# CuC_PSU.net
KiCad netlist of a schematic drawn in Altium Designer
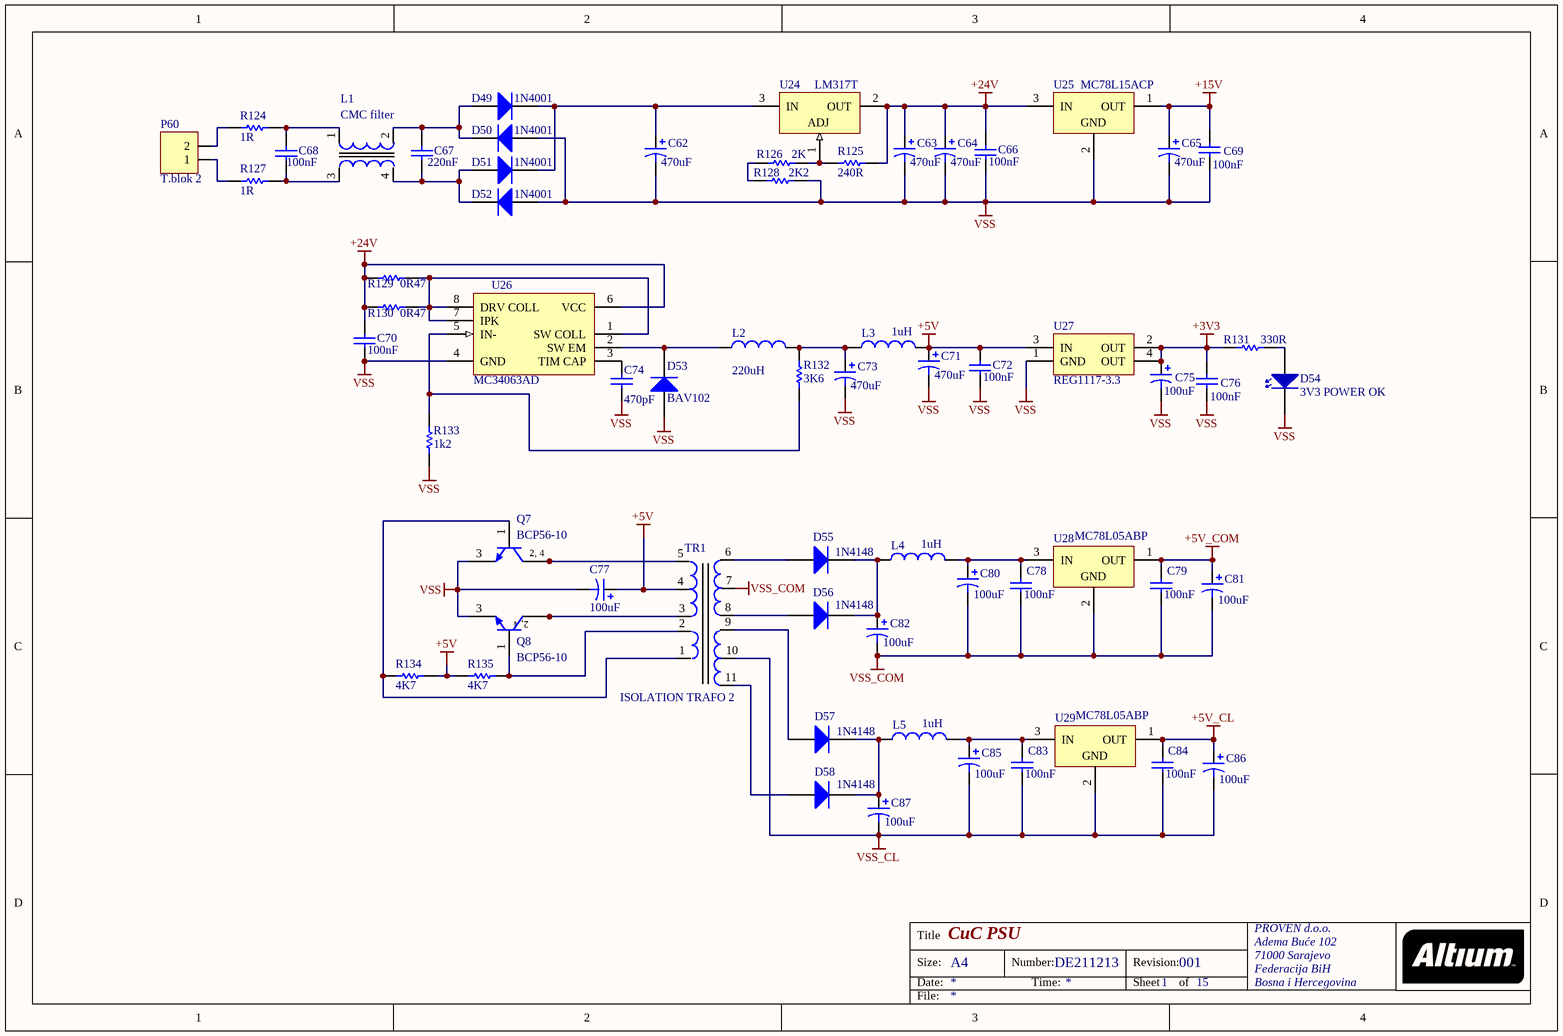
[diagram p0: CuC_PSU.SchDoc]

(export (version "E")
  (design (tool "Eeschema 10.0.6"))
  (components
    (comp (ref "C62")
      (value "470uF")
      (footprint "CAPPR5-10X16")
      (description "Aluminum Electrolytic Capacitor, Radial Style with Long Leads: 470uF, 35V")
      (fields (field (name "PUBLISHER") "Altium Limited"))
      (libsource (lib "Vishay Roederstein Electrolytic Radial-Lead Capacitor") (part "EKA00DD347F00"))
    )
    (comp (ref "C63")
      (value "470uF")
      (footprint "CAPPR5-10X16")
      (description "Aluminum Electrolytic Capacitor, Radial Style with Long Leads: 470uF, 35V")
      (fields (field (name "PUBLISHER") "Altium Limited"))
      (libsource (lib "Vishay Roederstein Electrolytic Radial-Lead Capacitor") (part "EKA00DD347F00"))
    )
    (comp (ref "C64")
      (value "470uF")
      (footprint "CAPPR5-10X16")
      (description "Aluminum Electrolytic Capacitor, Radial Style with Long Leads: 470uF, 35V")
      (fields (field (name "PUBLISHER") "Altium Limited"))
      (libsource (lib "Vishay Roederstein Electrolytic Radial-Lead Capacitor") (part "EKA00DD347F00"))
    )
    (comp (ref "C65")
      (value "470uF")
      (footprint "CAPPR5-10X16")
      (description "Aluminum Electrolytic Capacitor, Radial Style with Long Leads: 470uF, 35V")
      (fields (field (name "PUBLISHER") "Altium Limited"))
      (libsource (lib "Vishay Roederstein Electrolytic Radial-Lead Capacitor") (part "EKA00DD347F00"))
    )
    (comp (ref "C66")
      (value "100nF")
      (footprint "1206")
      (description "Ceramic Chip Capacitor - Standard")
      (fields (field (name "PUBLISHER") "Altium Limited"))
      (libsource (lib "KEMET Chip Capacitor") (part "C1206"))
    )
    (comp (ref "C67")
      (value "220nF")
      (footprint "VP60-3.6")
      (description "Dipped Radial Multilayer Ceramic Capacitor COG (NPO): 68nF, 50/63V")
      (fields (field (name "PUBLISHER") "Altium Limited"))
      (libsource (lib "Vishay Vitramon Ceramic Dipped Capacitor") (part "VP60BA683KA"))
    )
    (comp (ref "C68")
      (value "100nF")
      (footprint "VP60-3.6")
      (description "Dipped Radial Multilayer Ceramic Capacitor COG (NPO): 68nF, 50/63V")
      (fields (field (name "PUBLISHER") "Altium Limited"))
      (libsource (lib "Vishay Vitramon Ceramic Dipped Capacitor") (part "VP60BA683KA"))
    )
    (comp (ref "C69")
      (value "100nF")
      (footprint "1206")
      (description "Ceramic Chip Capacitor - Standard")
      (fields (field (name "PUBLISHER") "Altium Limited"))
      (libsource (lib "KEMET Chip Capacitor") (part "C1206"))
    )
    (comp (ref "C70")
      (value "100nF")
      (footprint "1206")
      (description "Ceramic Chip Capacitor - Standard")
      (fields (field (name "PUBLISHER") "Altium Limited"))
      (libsource (lib "KEMET Chip Capacitor") (part "C1206"))
    )
    (comp (ref "C71")
      (value "470uF")
      (footprint "CAPPR5-10X16")
      (description "Aluminum Electrolytic Capacitor, Radial Style with Long Leads: 470uF, 35V")
      (fields (field (name "PUBLISHER") "Altium Limited"))
      (libsource (lib "Vishay Roederstein Electrolytic Radial-Lead Capacitor") (part "EKA00DD347F00"))
    )
    (comp (ref "C72")
      (value "100nF")
      (footprint "1206")
      (description "Ceramic Chip Capacitor - Standard")
      (fields (field (name "PUBLISHER") "Altium Limited"))
      (libsource (lib "KEMET Chip Capacitor") (part "C1206"))
    )
    (comp (ref "C73")
      (value "470uF")
      (footprint "CAPPR5-10X16")
      (description "Aluminum Electrolytic Capacitor, Radial Style with Long Leads: 470uF, 35V")
      (fields (field (name "PUBLISHER") "Altium Limited"))
      (libsource (lib "Vishay Roederstein Electrolytic Radial-Lead Capacitor") (part "EKA00DD347F00"))
    )
    (comp (ref "C74")
      (value "470pF")
      (footprint "0805")
      (description "Ceramic Chip Capacitor - Standard")
      (fields (field (name "PUBLISHER") "Altium Limited"))
      (libsource (lib "KEMET Chip Capacitor") (part "C0805"))
    )
    (comp (ref "C75")
      (value "100uF")
      (footprint "CAPPR2-5X11")
      (description "Aluminum Electrolytic Capacitor, Radial Style with Long Leads: 100uF, 16V")
      (fields (field (name "PUBLISHER") "Altium Limited"))
      (libsource (lib "Vishay Roederstein Electrolytic Radial-Lead Capacitor") (part "EKA00AA310D00"))
    )
    (comp (ref "C76")
      (value "100nF")
      (footprint "1206")
      (description "Ceramic Chip Capacitor - Standard")
      (fields (field (name "PUBLISHER") "Altium Limited"))
      (libsource (lib "KEMET Chip Capacitor") (part "C1206"))
    )
    (comp (ref "C77")
      (value "100uF")
      (footprint "CAPPR2-5X11")
      (description "Aluminum Electrolytic Capacitor, Radial Style with Long Leads: 100uF, 16V")
      (fields (field (name "PUBLISHER") "Altium Limited"))
      (libsource (lib "Vishay Roederstein Electrolytic Radial-Lead Capacitor") (part "EKA00AA310D00"))
    )
    (comp (ref "C78")
      (value "100nF")
      (footprint "1206")
      (description "Ceramic Chip Capacitor - Standard")
      (fields (field (name "PUBLISHER") "Altium Limited"))
      (libsource (lib "KEMET Chip Capacitor") (part "C1206"))
    )
    (comp (ref "C79")
      (value "100nF")
      (footprint "1206")
      (description "Ceramic Chip Capacitor - Standard")
      (fields (field (name "PUBLISHER") "Altium Limited"))
      (libsource (lib "KEMET Chip Capacitor") (part "C1206"))
    )
    (comp (ref "C80")
      (value "100uF")
      (footprint "CAPPR2-5X11")
      (description "Aluminum Electrolytic Capacitor, Radial Style with Long Leads: 100uF, 16V")
      (fields (field (name "PUBLISHER") "Altium Limited"))
      (libsource (lib "Vishay Roederstein Electrolytic Radial-Lead Capacitor") (part "EKA00AA310D00"))
    )
    (comp (ref "C81")
      (value "100uF")
      (footprint "CAPPR2-5X11")
      (description "Aluminum Electrolytic Capacitor, Radial Style with Long Leads: 100uF, 16V")
      (fields (field (name "PUBLISHER") "Altium Limited"))
      (libsource (lib "Vishay Roederstein Electrolytic Radial-Lead Capacitor") (part "EKA00AA310D00"))
    )
    (comp (ref "C82")
      (value "100uF")
      (footprint "CAPPR2-5X11")
      (description "Aluminum Electrolytic Capacitor, Radial Style with Long Leads: 100uF, 16V")
      (fields (field (name "PUBLISHER") "Altium Limited"))
      (libsource (lib "Vishay Roederstein Electrolytic Radial-Lead Capacitor") (part "EKA00AA310D00"))
    )
    (comp (ref "C83")
      (value "100nF")
      (footprint "1206")
      (description "Ceramic Chip Capacitor - Standard")
      (fields (field (name "PUBLISHER") "Altium Limited"))
      (libsource (lib "KEMET Chip Capacitor") (part "C1206"))
    )
    (comp (ref "C84")
      (value "100nF")
      (footprint "1206")
      (description "Ceramic Chip Capacitor - Standard")
      (fields (field (name "PUBLISHER") "Altium Limited"))
      (libsource (lib "KEMET Chip Capacitor") (part "C1206"))
    )
    (comp (ref "C85")
      (value "100uF")
      (footprint "CAPPR2-5X11")
      (description "Aluminum Electrolytic Capacitor, Radial Style with Long Leads: 100uF, 16V")
      (fields (field (name "PUBLISHER") "Altium Limited"))
      (libsource (lib "Vishay Roederstein Electrolytic Radial-Lead Capacitor") (part "EKA00AA310D00"))
    )
    (comp (ref "C86")
      (value "100uF")
      (footprint "CAPPR2-5X11")
      (description "Aluminum Electrolytic Capacitor, Radial Style with Long Leads: 100uF, 16V")
      (fields (field (name "PUBLISHER") "Altium Limited"))
      (libsource (lib "Vishay Roederstein Electrolytic Radial-Lead Capacitor") (part "EKA00AA310D00"))
    )
    (comp (ref "C87")
      (value "100uF")
      (footprint "CAPPR2-5X11")
      (description "Aluminum Electrolytic Capacitor, Radial Style with Long Leads: 100uF, 16V")
      (fields (field (name "PUBLISHER") "Altium Limited"))
      (libsource (lib "Vishay Roederstein Electrolytic Radial-Lead Capacitor") (part "EKA00AA310D00"))
    )
    (comp (ref "D49")
      (value "1N4001")
      (footprint "DO-41")
      (description "1 Amp General Purpose Rectifier")
      (fields (field (name "PUBLISHER") "Altium Limited"))
      (libsource (lib "Miscellaneous Devices") (part "Diode 1N4007"))
    )
    (comp (ref "D50")
      (value "1N4001")
      (footprint "DO-41")
      (description "1 Amp General Purpose Rectifier")
      (fields (field (name "PUBLISHER") "Altium Limited"))
      (libsource (lib "Miscellaneous Devices") (part "Diode 1N4007"))
    )
    (comp (ref "D51")
      (value "1N4001")
      (footprint "DO-41")
      (description "1 Amp General Purpose Rectifier")
      (fields (field (name "PUBLISHER") "Altium Limited"))
      (libsource (lib "Miscellaneous Devices") (part "Diode 1N4007"))
    )
    (comp (ref "D52")
      (value "1N4001")
      (footprint "DO-41")
      (description "1 Amp General Purpose Rectifier")
      (fields (field (name "PUBLISHER") "Altium Limited"))
      (libsource (lib "Miscellaneous Devices") (part "Diode 1N4007"))
    )
    (comp (ref "D53")
      (value "BAV102")
      (footprint "SOD80C")
      (description "General-purpose Diode")
      (fields (field (name "PUBLISHER") "Altium Limited"))
      (libsource (lib "Philips Discrete Diode - Switching") (part "BAV102"))
    )
    (comp (ref "D54")
      (value "3V3 POWER OK")
      (footprint "LED 3mm")
      (libsource (lib "ProjectLibrary") (part "LED 3mm"))
    )
    (comp (ref "D55")
      (value "1N4148")
      (footprint "DO-35")
      (description "High Conductance Fast Diode")
      (fields (field (name "PUBLISHER") "Altium Limited"))
      (libsource (lib "Miscellaneous Devices") (part "Diode 1N4148"))
    )
    (comp (ref "D56")
      (value "1N4148")
      (footprint "DO-35")
      (description "High Conductance Fast Diode")
      (fields (field (name "PUBLISHER") "Altium Limited"))
      (libsource (lib "Miscellaneous Devices") (part "Diode 1N4148"))
    )
    (comp (ref "D57")
      (value "1N4148")
      (footprint "DO-35")
      (description "High Conductance Fast Diode")
      (fields (field (name "PUBLISHER") "Altium Limited"))
      (libsource (lib "Miscellaneous Devices") (part "Diode 1N4148"))
    )
    (comp (ref "D58")
      (value "1N4148")
      (footprint "DO-35")
      (description "High Conductance Fast Diode")
      (fields (field (name "PUBLISHER") "Altium Limited"))
      (libsource (lib "Miscellaneous Devices") (part "Diode 1N4148"))
    )
    (comp (ref "L1")
      (value "CMC filter")
      (footprint "MREZNI FILTER")
      (libsource (lib "ProjectLibrary") (part "MREZNI FILTER"))
    )
    (comp (ref "L2")
      (value "220uH")
      (footprint "Miscellaneous Devices:RB5-10.5")
      (description "SMT Power Choke Coil; Size 7.3×6.6×3.0mm, ±20% Tolerance, 0.82uH, 13A")
      (fields (field (name "PUBLISHER") "Altium Limited"))
      (libsource (lib "SSM Inductor") (part "PCMC063T-R82MN"))
    )
    (comp (ref "L3")
      (value "1uH")
      (footprint "Miscellaneous Devices:RB5-10.5")
      (description "SMT Power Choke Coil; Size 7.3×6.6×3.0mm, ±20% Tolerance, 0.82uH, 13A")
      (fields (field (name "PUBLISHER") "Altium Limited"))
      (libsource (lib "SSM Inductor") (part "PCMC063T-R82MN"))
    )
    (comp (ref "L4")
      (value "1uH")
      (footprint "Miscellaneous Devices:RB5-10.5")
      (description "SMT Power Choke Coil; Size 7.3×6.6×3.0mm, ±20% Tolerance, 0.82uH, 13A")
      (fields (field (name "PUBLISHER") "Altium Limited"))
      (libsource (lib "SSM Inductor") (part "PCMC063T-R82MN"))
    )
    (comp (ref "L5")
      (value "1uH")
      (footprint "Miscellaneous Devices:RB5-10.5")
      (description "SMT Power Choke Coil; Size 7.3×6.6×3.0mm, ±20% Tolerance, 0.82uH, 13A")
      (fields (field (name "PUBLISHER") "Altium Limited"))
      (libsource (lib "SSM Inductor") (part "PCMC063T-R82MN"))
    )
    (comp (ref "P60")
      (value "T.blok 2")
      (footprint "TERMINAL BLOK 2")
      (description "Terminal blok konektor 3,5 mm")
      (libsource (lib "ProjectLibrary") (part "TERMINAL BLOK 2"))
    )
    (comp (ref "Q7")
      (value "BCP56-10")
      (footprint "SOT223_N")
      (description "NPN Medium Power Transistor")
      (fields (field (name "PUBLISHER") "Altium Limited"))
      (libsource (lib "Philips Discrete BJT - Medium Power") (part "BCP56-10"))
    )
    (comp (ref "Q8")
      (value "BCP56-10")
      (footprint "SOT223_N")
      (description "NPN Medium Power Transistor")
      (fields (field (name "PUBLISHER") "Altium Limited"))
      (libsource (lib "Philips Discrete BJT - Medium Power") (part "BCP56-10"))
    )
    (comp (ref "R124")
      (value "1R")
      (footprint "R6.35x2.3")
      (description "Metal Oxide Film Resistor, 0.1 Ohm to 47k Ohm Range, 2% and 5% Tolerance, 0.5 W")
      (fields (field (name "PUBLISHER") "Altium Limited"))
      (libsource (lib "Panasonic Resistor") (part "ERG12"))
    )
    (comp (ref "R125")
      (value "240R")
      (footprint "ERA-0805")
      (fields (field (name "PUBLISHER") "Altium Limited"))
      (libsource (lib "Panasonic Resistor") (part "ERAS"))
    )
    (comp (ref "R126")
      (value "2K")
      (footprint "ERA-0805")
      (fields (field (name "PUBLISHER") "Altium Limited"))
      (libsource (lib "Panasonic Resistor") (part "ERAS"))
    )
    (comp (ref "R127")
      (value "1R")
      (footprint "R6.35x2.3")
      (description "Metal Oxide Film Resistor, 0.1 Ohm to 47k Ohm Range, 2% and 5% Tolerance, 0.5 W")
      (fields (field (name "PUBLISHER") "Altium Limited"))
      (libsource (lib "Panasonic Resistor") (part "ERG12"))
    )
    (comp (ref "R128")
      (value "2K2")
      (footprint "ERA-0805")
      (fields (field (name "PUBLISHER") "Altium Limited"))
      (libsource (lib "Panasonic Resistor") (part "ERAS"))
    )
    (comp (ref "R129")
      (value "0R47")
      (footprint "RD6.35x2.3")
      (description "Carbon Film Resistor, 1 Ohm to 3.3M Ohm Range, 5% Tolerance, 0.5 W")
      (fields (field (name "PUBLISHER") "Altium Limited"))
      (libsource (lib "Panasonic Resistor") (part "ERDS1T"))
    )
    (comp (ref "R130")
      (value "0R47")
      (footprint "RD6.35x2.3")
      (description "Carbon Film Resistor, 1 Ohm to 3.3M Ohm Range, 5% Tolerance, 0.5 W")
      (fields (field (name "PUBLISHER") "Altium Limited"))
      (libsource (lib "Panasonic Resistor") (part "ERDS1T"))
    )
    (comp (ref "R131")
      (value "330R")
      (footprint "ERA-0603")
      (fields (field (name "PUBLISHER") "Altium Limited"))
      (libsource (lib "Panasonic Resistor") (part "ERA3Y"))
    )
    (comp (ref "R132")
      (value "3K6")
      (footprint "ERA-0805")
      (fields (field (name "PUBLISHER") "Altium Limited"))
      (libsource (lib "Panasonic Resistor") (part "ERAS"))
    )
    (comp (ref "R133")
      (value "1k2")
      (footprint "ERA-0805")
      (fields (field (name "PUBLISHER") "Altium Limited"))
      (libsource (lib "Panasonic Resistor") (part "ERAS"))
    )
    (comp (ref "R134")
      (value "4K7")
      (footprint "ERA-0805")
      (fields (field (name "PUBLISHER") "Altium Limited"))
      (libsource (lib "Panasonic Resistor") (part "ERAS"))
    )
    (comp (ref "R135")
      (value "4K7")
      (footprint "ERA-0805")
      (fields (field (name "PUBLISHER") "Altium Limited"))
      (libsource (lib "Panasonic Resistor") (part "ERAS"))
    )
    (comp (ref "TR1")
      (value "ISOLATION TRAFO 2")
      (footprint "ISOLATION TRAFO 2")
      (libsource (lib "ProjectLibrary") (part "ISOLATION TRAFO 2"))
    )
    (comp (ref "U24")
      (value "LM317T")
      (footprint "221A-04")
      (description "3-Terminal Adjustable Positive Voltage Regulator")
      (fields (field (name "PUBLISHER") "Altium Limited"))
      (libsource (lib "Motorola Power Mgt Voltage Regulator") (part "LM317T"))
    )
    (comp (ref "U25")
      (value "MC78L15ACP")
      (footprint "29-04")
      (description "3-Terminal Low-Current Positive Fixed Voltage Regulator")
      (fields (field (name "PUBLISHER") "Altium Limited"))
      (libsource (lib "Motorola Power Mgt Voltage Regulator") (part "MC78L15ACP"))
    )
    (comp (ref "U26")
      (value "MC34063AD")
      (footprint "ON Semi Power Mgt Supervisory Cct:626-05")
      (description "DC-to-DC Converter Control Circuit")
      (fields (field (name "PUBLISHER") "Altium Limited"))
      (libsource (lib "ON Semi Power Mgt DC-DC Converter") (part "MC34063AD"))
    )
    (comp (ref "U27")
      (value "REG1117-3.3")
      (footprint "ZZ311")
      (description "800mA and 1A Low Dropout Positive Regulator 2.85V, 3.3V, 5V, and Adjustable")
      (fields (field (name "PUBLISHER") "Altium Limited"))
      (libsource (lib "BB Power Mgt Voltage Regulator") (part "REG1117-3.3"))
    )
    (comp (ref "U28")
      (value "MC78L05ABP")
      (footprint "29-04")
      (description "3-Terminal Low-Current Positive Fixed Voltage Regulator")
      (fields (field (name "PUBLISHER") "Altium Limited"))
      (libsource (lib "Motorola Power Mgt Voltage Regulator") (part "MC78L05ABP"))
    )
    (comp (ref "U29")
      (value "MC78L05ABP")
      (footprint "29-04")
      (description "3-Terminal Low-Current Positive Fixed Voltage Regulator")
      (fields (field (name "PUBLISHER") "Altium Limited"))
      (libsource (lib "Motorola Power Mgt Voltage Regulator") (part "MC78L05ABP"))
    )
  )
  (nets
    (net (code "1") (name "+3V3") (class "Default")
      (node (ref "C75") (pin "1") (pinfunction "1_1") (pintype "passive"))
      (node (ref "C76") (pin "2") (pinfunction "2_2") (pintype "passive"))
      (node (ref "R131") (pin "1") (pinfunction "1_1") (pintype "passive"))
      (node (ref "U27") (pin "2") (pinfunction "OUT_2") (pintype "power_in"))
      (node (ref "U27") (pin "4") (pinfunction "OUT_4") (pintype "power_in"))
    )
    (net (code "2") (name "+5V") (class "Default")
      (node (ref "C71") (pin "1") (pinfunction "1_1") (pintype "passive"))
      (node (ref "C72") (pin "2") (pinfunction "2_2") (pintype "passive"))
      (node (ref "C77") (pin "1") (pinfunction "1_1") (pintype "passive"))
      (node (ref "L3") (pin "2") (pinfunction "2_2") (pintype "passive"))
      (node (ref "R134") (pin "1") (pinfunction "1_1") (pintype "passive"))
      (node (ref "R135") (pin "2") (pinfunction "2_2") (pintype "passive"))
      (node (ref "TR1") (pin "4") (pinfunction "4_4") (pintype "passive"))
      (node (ref "U27") (pin "3") (pinfunction "IN_3") (pintype "power_in"))
    )
    (net (code "3") (name "+5V_CL") (class "Default")
      (node (ref "C84") (pin "2") (pinfunction "2_2") (pintype "passive"))
      (node (ref "C86") (pin "1") (pinfunction "1_1") (pintype "passive"))
      (node (ref "U29") (pin "1") (pinfunction "OUT_1") (pintype "power_in"))
    )
    (net (code "4") (name "+5V_COM") (class "Default")
      (node (ref "C79") (pin "2") (pinfunction "2_2") (pintype "passive"))
      (node (ref "C81") (pin "1") (pinfunction "1_1") (pintype "passive"))
      (node (ref "U28") (pin "1") (pinfunction "OUT_1") (pintype "power_in"))
    )
    (net (code "5") (name "+15V") (class "Default")
      (node (ref "C65") (pin "1") (pinfunction "1_1") (pintype "passive"))
      (node (ref "C69") (pin "2") (pinfunction "2_2") (pintype "passive"))
      (node (ref "U25") (pin "1") (pinfunction "OUT_1") (pintype "power_in"))
    )
    (net (code "6") (name "+24V") (class "Default")
      (node (ref "C63") (pin "1") (pinfunction "1_1") (pintype "passive"))
      (node (ref "C64") (pin "1") (pinfunction "1_1") (pintype "passive"))
      (node (ref "C66") (pin "2") (pinfunction "2_2") (pintype "passive"))
      (node (ref "C70") (pin "2") (pinfunction "2_2") (pintype "passive"))
      (node (ref "R125") (pin "1") (pinfunction "1_1") (pintype "passive"))
      (node (ref "R129") (pin "1") (pinfunction "1_1") (pintype "passive"))
      (node (ref "R130") (pin "1") (pinfunction "1_1") (pintype "passive"))
      (node (ref "U24") (pin "2") (pinfunction "OUT_2") (pintype "power_in"))
      (node (ref "U25") (pin "3") (pinfunction "IN_3") (pintype "power_in"))
      (node (ref "U26") (pin "6") (pinfunction "VCC_6") (pintype "power_in"))
    )
    (net (code "7") (name "Net-(C68-Pad1)") (class "Default")
      (node (ref "C68") (pin "1") (pinfunction "1_1") (pintype "passive"))
      (node (ref "L1") (pin "3") (pintype "passive"))
      (node (ref "R127") (pin "1") (pinfunction "1_1") (pintype "passive"))
    )
    (net (code "8") (name "Net-(C68-Pad2)") (class "Default")
      (node (ref "C68") (pin "2") (pinfunction "2_2") (pintype "passive"))
      (node (ref "L1") (pin "1") (pintype "passive"))
      (node (ref "R124") (pin "1") (pinfunction "1_1") (pintype "passive"))
    )
    (net (code "9") (name "Net-(C73-Pad1)") (class "Default")
      (node (ref "C73") (pin "1") (pinfunction "1_1") (pintype "passive"))
      (node (ref "L2") (pin "2") (pinfunction "2_2") (pintype "passive"))
      (node (ref "L3") (pin "1") (pinfunction "1_1") (pintype "passive"))
      (node (ref "R132") (pin "2") (pinfunction "2_2") (pintype "passive"))
    )
    (net (code "10") (name "Net-(D49-A)") (class "Default")
      (node (ref "C67") (pin "2") (pinfunction "2_2") (pintype "passive"))
      (node (ref "D49") (pin "1") (pinfunction "A_1") (pintype "passive"))
      (node (ref "D50") (pin "2") (pinfunction "K_2") (pintype "passive"))
      (node (ref "L1") (pin "2") (pintype "passive"))
    )
    (net (code "11") (name "Net-(D49-K)") (class "Default")
      (node (ref "C62") (pin "1") (pinfunction "1_1") (pintype "passive"))
      (node (ref "D49") (pin "2") (pinfunction "K_2") (pintype "passive"))
      (node (ref "D51") (pin "2") (pinfunction "K_2") (pintype "passive"))
      (node (ref "U24") (pin "3") (pinfunction "IN_3") (pintype "power_in"))
    )
    (net (code "12") (name "Net-(D51-A)") (class "Default")
      (node (ref "C67") (pin "1") (pinfunction "1_1") (pintype "passive"))
      (node (ref "D51") (pin "1") (pinfunction "A_1") (pintype "passive"))
      (node (ref "D52") (pin "2") (pinfunction "K_2") (pintype "passive"))
      (node (ref "L1") (pin "4") (pintype "passive"))
    )
    (net (code "13") (name "Net-(D53-K)") (class "Default")
      (node (ref "D53") (pin "2") (pinfunction "K_2") (pintype "passive"))
      (node (ref "L2") (pin "1") (pinfunction "1_1") (pintype "passive"))
      (node (ref "U26") (pin "2") (pinfunction "SW_EM_2") (pintype "passive"))
    )
    (net (code "14") (name "Net-(D54-Pad2)") (class "Default")
      (node (ref "D54") (pin "2") (pinfunction "2_2") (pintype "passive"))
      (node (ref "R131") (pin "2") (pinfunction "2_2") (pintype "passive"))
    )
    (net (code "15") (name "Net-(D55-A)") (class "Default")
      (node (ref "D55") (pin "1") (pinfunction "A_1") (pintype "passive"))
      (node (ref "TR1") (pin "6") (pinfunction "6_6") (pintype "passive"))
    )
    (net (code "16") (name "Net-(D55-K)") (class "Default")
      (node (ref "C82") (pin "1") (pinfunction "1_1") (pintype "passive"))
      (node (ref "D55") (pin "2") (pinfunction "K_2") (pintype "passive"))
      (node (ref "D56") (pin "2") (pinfunction "K_2") (pintype "passive"))
      (node (ref "L4") (pin "1") (pinfunction "1_1") (pintype "passive"))
    )
    (net (code "17") (name "Net-(D56-A)") (class "Default")
      (node (ref "D56") (pin "1") (pinfunction "A_1") (pintype "passive"))
      (node (ref "TR1") (pin "8") (pinfunction "8_8") (pintype "passive"))
    )
    (net (code "18") (name "Net-(D57-A)") (class "Default")
      (node (ref "D57") (pin "1") (pinfunction "A_1") (pintype "passive"))
      (node (ref "TR1") (pin "9") (pinfunction "9_9") (pintype "passive"))
    )
    (net (code "19") (name "Net-(D57-K)") (class "Default")
      (node (ref "C87") (pin "1") (pinfunction "1_1") (pintype "passive"))
      (node (ref "D57") (pin "2") (pinfunction "K_2") (pintype "passive"))
      (node (ref "D58") (pin "2") (pinfunction "K_2") (pintype "passive"))
      (node (ref "L5") (pin "1") (pinfunction "1_1") (pintype "passive"))
    )
    (net (code "20") (name "Net-(D58-A)") (class "Default")
      (node (ref "D58") (pin "1") (pinfunction "A_1") (pintype "passive"))
      (node (ref "TR1") (pin "11") (pinfunction "11_11") (pintype "passive"))
    )
    (net (code "21") (name "Net-(P60-Pad1)") (class "Default")
      (node (ref "P60") (pin "1") (pinfunction "1_1") (pintype "passive"))
      (node (ref "R127") (pin "2") (pinfunction "2_2") (pintype "passive"))
    )
    (net (code "22") (name "Net-(P60-Pad2)") (class "Default")
      (node (ref "P60") (pin "2") (pinfunction "2_2") (pintype "passive"))
      (node (ref "R124") (pin "2") (pinfunction "2_2") (pintype "passive"))
    )
    (net (code "23") (name "Net-(Q7-B)") (class "Default")
      (node (ref "Q7") (pin "1") (pinfunction "B_1") (pintype "passive"))
      (node (ref "R134") (pin "2") (pinfunction "2_2") (pintype "passive"))
      (node (ref "TR1") (pin "1") (pinfunction "1_1") (pintype "passive"))
    )
    (net (code "24") (name "Net-(Q7-C-Pad2)") (class "Default")
      (node (ref "Q7") (pin "2") (pinfunction "C_2") (pintype "passive"))
      (node (ref "Q7") (pin "4") (pinfunction "C_4") (pintype "passive"))
      (node (ref "TR1") (pin "5") (pinfunction "5_5") (pintype "passive"))
    )
    (net (code "25") (name "Net-(Q8-B)") (class "Default")
      (node (ref "Q8") (pin "1") (pinfunction "B_1") (pintype "passive"))
      (node (ref "R135") (pin "1") (pinfunction "1_1") (pintype "passive"))
      (node (ref "TR1") (pin "2") (pinfunction "2_2") (pintype "passive"))
    )
    (net (code "26") (name "Net-(Q8-C-Pad2)") (class "Default")
      (node (ref "Q8") (pin "2") (pinfunction "C_2") (pintype "passive"))
      (node (ref "Q8") (pin "4") (pinfunction "C_4") (pintype "passive"))
      (node (ref "TR1") (pin "3") (pinfunction "3_3") (pintype "passive"))
    )
    (net (code "27") (name "Net-(R126-Pad1)") (class "Default")
      (node (ref "R126") (pin "1") (pinfunction "1_1") (pintype "passive"))
      (node (ref "R128") (pin "2") (pinfunction "2_2") (pintype "passive"))
    )
    (net (code "28") (name "Net-(U24-ADJ)") (class "Default")
      (node (ref "R125") (pin "2") (pinfunction "2_2") (pintype "passive"))
      (node (ref "R126") (pin "2") (pinfunction "2_2") (pintype "passive"))
      (node (ref "U24") (pin "1") (pinfunction "ADJ_1") (pintype "input"))
    )
    (net (code "29") (name "Net-(U26-DRV_COLL)") (class "Default")
      (node (ref "R129") (pin "2") (pinfunction "2_2") (pintype "passive"))
      (node (ref "R130") (pin "2") (pinfunction "2_2") (pintype "passive"))
      (node (ref "U26") (pin "1") (pinfunction "SW_COLL_1") (pintype "passive"))
      (node (ref "U26") (pin "7") (pinfunction "IPK_7") (pintype "passive"))
      (node (ref "U26") (pin "8") (pinfunction "DRV_COLL_8") (pintype "open_collector"))
    )
    (net (code "30") (name "Net-(U26-IN-)") (class "Default")
      (node (ref "R132") (pin "1") (pinfunction "1_1") (pintype "passive"))
      (node (ref "R133") (pin "2") (pinfunction "2_2") (pintype "passive"))
      (node (ref "U26") (pin "5") (pinfunction "IN-_5") (pintype "input"))
    )
    (net (code "31") (name "Net-(U26-TIM_CAP)") (class "Default")
      (node (ref "C74") (pin "2") (pinfunction "2_2") (pintype "passive"))
      (node (ref "U26") (pin "3") (pinfunction "TIM_CAP_3") (pintype "passive"))
    )
    (net (code "32") (name "Net-(U28-IN)") (class "Default")
      (node (ref "C78") (pin "2") (pinfunction "2_2") (pintype "passive"))
      (node (ref "C80") (pin "1") (pinfunction "1_1") (pintype "passive"))
      (node (ref "L4") (pin "2") (pinfunction "2_2") (pintype "passive"))
      (node (ref "U28") (pin "3") (pinfunction "IN_3") (pintype "power_in"))
    )
    (net (code "33") (name "Net-(U29-IN)") (class "Default")
      (node (ref "C83") (pin "2") (pinfunction "2_2") (pintype "passive"))
      (node (ref "C85") (pin "1") (pinfunction "1_1") (pintype "passive"))
      (node (ref "L5") (pin "2") (pinfunction "2_2") (pintype "passive"))
      (node (ref "U29") (pin "3") (pinfunction "IN_3") (pintype "power_in"))
    )
    (net (code "34") (name "VSS") (class "Default")
      (node (ref "C62") (pin "2") (pinfunction "2_2") (pintype "passive"))
      (node (ref "C63") (pin "2") (pinfunction "2_2") (pintype "passive"))
      (node (ref "C64") (pin "2") (pinfunction "2_2") (pintype "passive"))
      (node (ref "C65") (pin "2") (pinfunction "2_2") (pintype "passive"))
      (node (ref "C66") (pin "1") (pinfunction "1_1") (pintype "passive"))
      (node (ref "C69") (pin "1") (pinfunction "1_1") (pintype "passive"))
      (node (ref "C70") (pin "1") (pinfunction "1_1") (pintype "passive"))
      (node (ref "C71") (pin "2") (pinfunction "2_2") (pintype "passive"))
      (node (ref "C72") (pin "1") (pinfunction "1_1") (pintype "passive"))
      (node (ref "C73") (pin "2") (pinfunction "2_2") (pintype "passive"))
      (node (ref "C74") (pin "1") (pinfunction "1_1") (pintype "passive"))
      (node (ref "C75") (pin "2") (pinfunction "2_2") (pintype "passive"))
      (node (ref "C76") (pin "1") (pinfunction "1_1") (pintype "passive"))
      (node (ref "C77") (pin "2") (pinfunction "2_2") (pintype "passive"))
      (node (ref "D50") (pin "1") (pinfunction "A_1") (pintype "passive"))
      (node (ref "D52") (pin "1") (pinfunction "A_1") (pintype "passive"))
      (node (ref "D53") (pin "1") (pinfunction "A_1") (pintype "passive"))
      (node (ref "D54") (pin "1") (pinfunction "1_1") (pintype "passive"))
      (node (ref "Q7") (pin "3") (pinfunction "E_3") (pintype "passive"))
      (node (ref "Q8") (pin "3") (pinfunction "E_3") (pintype "passive"))
      (node (ref "R128") (pin "1") (pinfunction "1_1") (pintype "passive"))
      (node (ref "R133") (pin "1") (pinfunction "1_1") (pintype "passive"))
      (node (ref "U25") (pin "2") (pinfunction "GND_2") (pintype "power_in"))
      (node (ref "U26") (pin "4") (pinfunction "GND_4") (pintype "power_in"))
      (node (ref "U27") (pin "1") (pinfunction "GND_1") (pintype "power_in"))
    )
    (net (code "35") (name "VSS_CL") (class "Default")
      (node (ref "C83") (pin "1") (pinfunction "1_1") (pintype "passive"))
      (node (ref "C84") (pin "1") (pinfunction "1_1") (pintype "passive"))
      (node (ref "C85") (pin "2") (pinfunction "2_2") (pintype "passive"))
      (node (ref "C86") (pin "2") (pinfunction "2_2") (pintype "passive"))
      (node (ref "C87") (pin "2") (pinfunction "2_2") (pintype "passive"))
      (node (ref "TR1") (pin "10") (pinfunction "10_10") (pintype "passive"))
      (node (ref "U29") (pin "2") (pinfunction "GND_2") (pintype "power_in"))
    )
    (net (code "36") (name "VSS_COM") (class "Default")
      (node (ref "C78") (pin "1") (pinfunction "1_1") (pintype "passive"))
      (node (ref "C79") (pin "1") (pinfunction "1_1") (pintype "passive"))
      (node (ref "C80") (pin "2") (pinfunction "2_2") (pintype "passive"))
      (node (ref "C81") (pin "2") (pinfunction "2_2") (pintype "passive"))
      (node (ref "C82") (pin "2") (pinfunction "2_2") (pintype "passive"))
      (node (ref "TR1") (pin "7") (pinfunction "7_7") (pintype "passive"))
      (node (ref "U28") (pin "2") (pinfunction "GND_2") (pintype "power_in"))
    )
  )
)
